# CanBus1apr.net
KiCad netlist of a schematic drawn in EAGLE
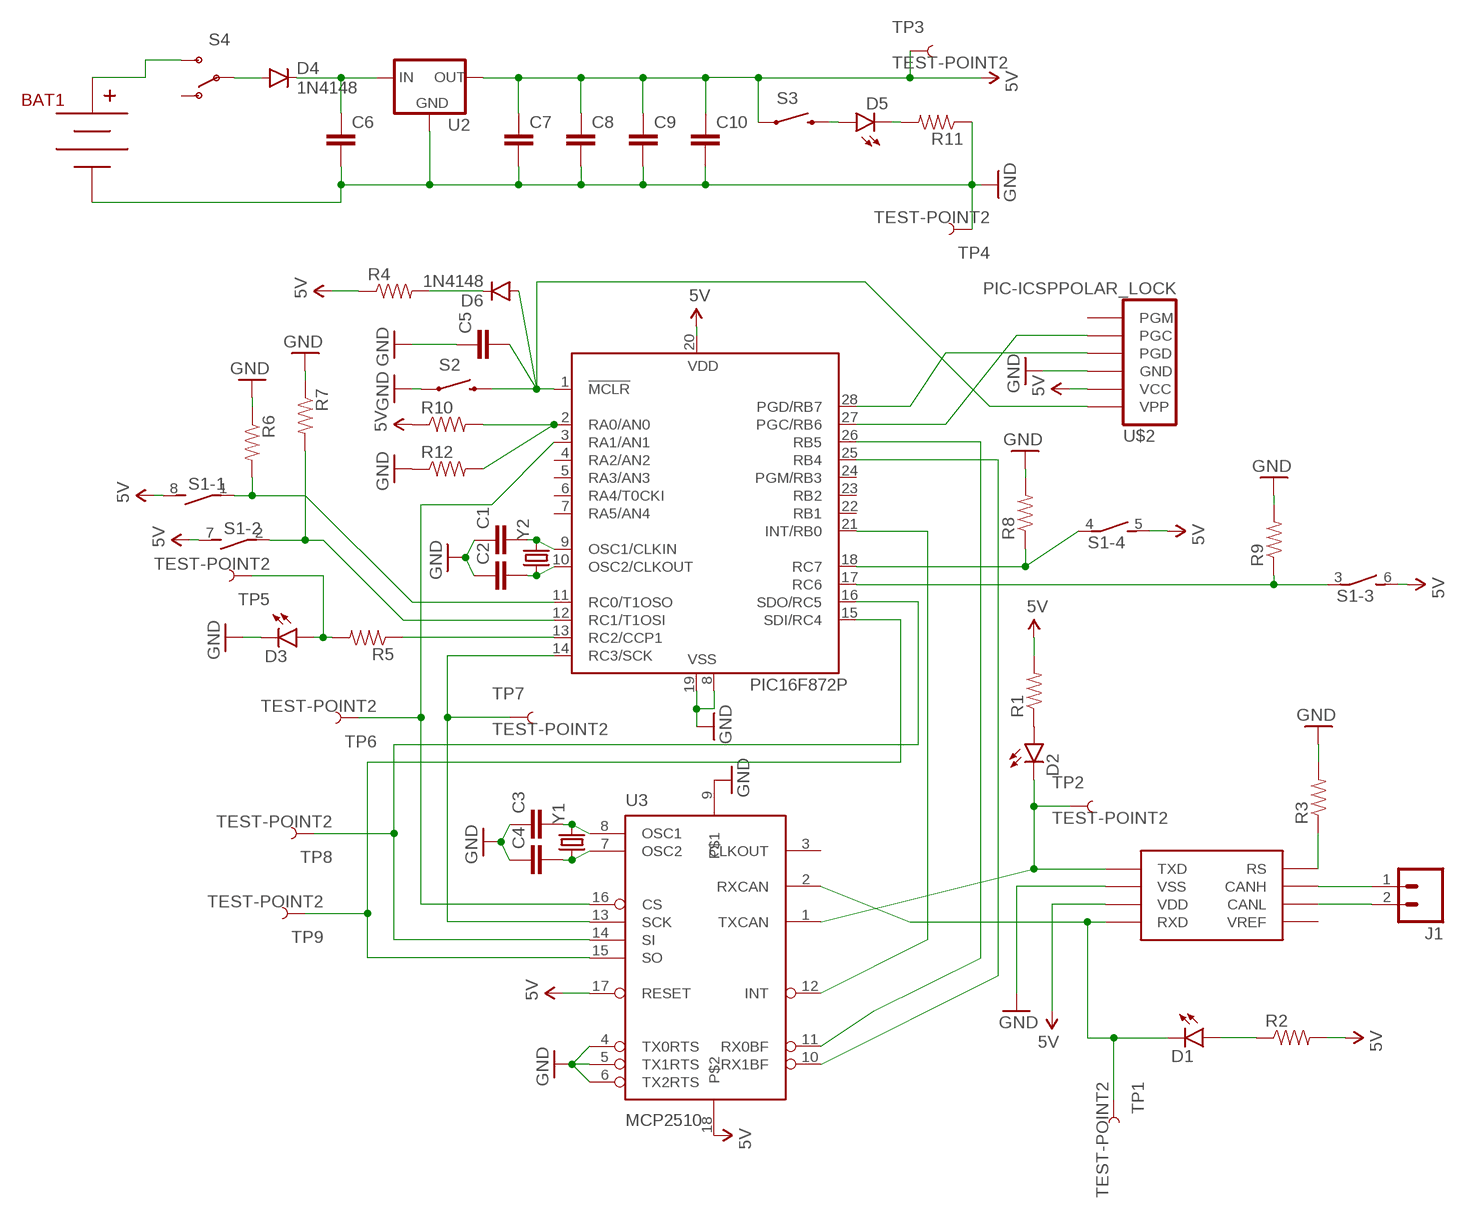
[diagram p0: schematic, sheet 1]

(export (version "E")
  (design (tool "Eeschema 10.0.6"))
  (components
    (comp (ref "BAT1")
      (value "BC9VPC")
      (footprint "eagle-import:BC9VPC")
      (libsource (lib "eagle-import") (part "BC9VPC"))
    )
    (comp (ref "C1")
      (value "CAPPTH")
      (footprint "eagle-import:CAP-PTH-SMALL")
      (libsource (lib "eagle-import") (part "CAPPTH"))
    )
    (comp (ref "C2")
      (value "CAPPTH")
      (footprint "eagle-import:CAP-PTH-SMALL")
      (libsource (lib "eagle-import") (part "CAPPTH"))
    )
    (comp (ref "C3")
      (value "CAPPTH")
      (footprint "eagle-import:CAP-PTH-SMALL")
      (libsource (lib "eagle-import") (part "CAPPTH"))
    )
    (comp (ref "C4")
      (value "CAPPTH")
      (footprint "eagle-import:CAP-PTH-SMALL")
      (libsource (lib "eagle-import") (part "CAPPTH"))
    )
    (comp (ref "C5")
      (value "CAPPTH")
      (footprint "eagle-import:CAP-PTH-SMALL")
      (libsource (lib "eagle-import") (part "CAPPTH"))
    )
    (comp (ref "C6")
      (value "CAPPTH")
      (footprint "eagle-import:CAP-PTH-SMALL")
      (libsource (lib "eagle-import") (part "CAPPTH"))
    )
    (comp (ref "C7")
      (value "CAPPTH")
      (footprint "eagle-import:CAP-PTH-SMALL")
      (libsource (lib "eagle-import") (part "CAPPTH"))
    )
    (comp (ref "C8")
      (value "CAPPTH")
      (footprint "eagle-import:CAP-PTH-SMALL")
      (libsource (lib "eagle-import") (part "CAPPTH"))
    )
    (comp (ref "C9")
      (value "CAPPTH")
      (footprint "eagle-import:CAP-PTH-SMALL")
      (libsource (lib "eagle-import") (part "CAPPTH"))
    )
    (comp (ref "C10")
      (value "CAPPTH")
      (footprint "eagle-import:CAP-PTH-SMALL")
      (libsource (lib "eagle-import") (part "CAPPTH"))
    )
    (comp (ref "D1")
      (value "LED5MM")
      (footprint "eagle-import:LED5MM")
      (libsource (lib "eagle-import") (part "LED5MM"))
    )
    (comp (ref "D2")
      (value "LED5MM")
      (footprint "eagle-import:LED5MM")
      (libsource (lib "eagle-import") (part "LED5MM"))
    )
    (comp (ref "D3")
      (value "LED5MM")
      (footprint "eagle-import:LED5MM")
      (libsource (lib "eagle-import") (part "LED5MM"))
    )
    (comp (ref "D4")
      (value "1N4148")
      (footprint "eagle-import:DIODE-1N4148-KIT")
      (libsource (lib "eagle-import") (part "DIODEKIT"))
    )
    (comp (ref "D5")
      (value "LED5MM")
      (footprint "eagle-import:LED5MM")
      (libsource (lib "eagle-import") (part "LED5MM"))
    )
    (comp (ref "D6")
      (value "1N4148")
      (footprint "eagle-import:DIODE-1N4148-KIT")
      (libsource (lib "eagle-import") (part "DIODEKIT"))
    )
    (comp (ref "IC1")
      (value "PIC16F872P")
      (footprint "eagle-import:DIL28-3")
      (fields (field (name "MF") "MICROCHIP") (field (name "MPN") "PIC16F872-I/SP"))
      (libsource (lib "eagle-import") (part "PIC16872PF"))
    )
    (comp (ref "J1")
      (value "M02PTH")
      (footprint "eagle-import:1X02")
      (libsource (lib "eagle-import") (part "M02PTH"))
    )
    (comp (ref "R1")
      (value "RESISTOREZ")
      (footprint "eagle-import:AXIAL-0.3EZ")
      (libsource (lib "eagle-import") (part "RESISTOREZ"))
    )
    (comp (ref "R2")
      (value "RESISTOREZ")
      (footprint "eagle-import:AXIAL-0.3EZ")
      (libsource (lib "eagle-import") (part "RESISTOREZ"))
    )
    (comp (ref "R3")
      (value "RESISTOREZ")
      (footprint "eagle-import:AXIAL-0.3EZ")
      (libsource (lib "eagle-import") (part "RESISTOREZ"))
    )
    (comp (ref "R4")
      (value "RESISTOREZ")
      (footprint "eagle-import:AXIAL-0.3EZ")
      (libsource (lib "eagle-import") (part "RESISTOREZ"))
    )
    (comp (ref "R5")
      (value "RESISTOREZ")
      (footprint "eagle-import:AXIAL-0.3EZ")
      (libsource (lib "eagle-import") (part "RESISTOREZ"))
    )
    (comp (ref "R6")
      (value "RESISTOREZ")
      (footprint "eagle-import:AXIAL-0.3EZ")
      (libsource (lib "eagle-import") (part "RESISTOREZ"))
    )
    (comp (ref "R7")
      (value "RESISTOREZ")
      (footprint "eagle-import:AXIAL-0.3EZ")
      (libsource (lib "eagle-import") (part "RESISTOREZ"))
    )
    (comp (ref "R8")
      (value "RESISTOREZ")
      (footprint "eagle-import:AXIAL-0.3EZ")
      (libsource (lib "eagle-import") (part "RESISTOREZ"))
    )
    (comp (ref "R9")
      (value "RESISTOREZ")
      (footprint "eagle-import:AXIAL-0.3EZ")
      (libsource (lib "eagle-import") (part "RESISTOREZ"))
    )
    (comp (ref "R10")
      (value "RESISTOREZ")
      (footprint "eagle-import:AXIAL-0.3EZ")
      (libsource (lib "eagle-import") (part "RESISTOREZ"))
    )
    (comp (ref "R11")
      (value "RESISTOREZ")
      (footprint "eagle-import:AXIAL-0.3EZ")
      (libsource (lib "eagle-import") (part "RESISTOREZ"))
    )
    (comp (ref "R12")
      (value "RESISTORAXIAL-0.3")
      (footprint "eagle-import:AXIAL-0.3")
      (libsource (lib "eagle-import") (part "SparkFun-Resistors_RESISTORAXIAL-0.3"))
    )
    (comp (ref "S1")
      (value "DIP04S")
      (footprint "eagle-import:DIP04S")
      (libsource (lib "eagle-import") (part "DIP04S"))
    )
    (comp (ref "S2")
      (value "SWITCH-MOMENTARY-2PTH")
      (footprint "eagle-import:TACTILE-PTH")
      (libsource (lib "eagle-import") (part "SWITCH-MOMENTARY-2PTH"))
    )
    (comp (ref "S3")
      (value "SWITCH-MOMENTARY-2PTH")
      (footprint "eagle-import:TACTILE-PTH")
      (libsource (lib "eagle-import") (part "SWITCH-MOMENTARY-2PTH"))
    )
    (comp (ref "S4")
      (value "SWITCH-SPDTKIT")
      (footprint "eagle-import:SWITCH-SPDT_KIT")
      (libsource (lib "eagle-import") (part "SWITCH-SPDTKIT"))
    )
    (comp (ref "TP1")
      (value "TEST-POINT2")
      (footprint "eagle-import:PAD.02X.02")
      (libsource (lib "eagle-import") (part "TEST-POINT2"))
    )
    (comp (ref "TP2")
      (value "TEST-POINT2")
      (footprint "eagle-import:PAD.02X.02")
      (libsource (lib "eagle-import") (part "TEST-POINT2"))
    )
    (comp (ref "TP3")
      (value "TEST-POINT2")
      (footprint "eagle-import:PAD.02X.02")
      (libsource (lib "eagle-import") (part "TEST-POINT2"))
    )
    (comp (ref "TP4")
      (value "TEST-POINT2")
      (footprint "eagle-import:PAD.02X.02")
      (libsource (lib "eagle-import") (part "TEST-POINT2"))
    )
    (comp (ref "TP5")
      (value "TEST-POINT2")
      (footprint "eagle-import:PAD.02X.02")
      (libsource (lib "eagle-import") (part "TEST-POINT2"))
    )
    (comp (ref "TP6")
      (value "TEST-POINT2")
      (footprint "eagle-import:PAD.02X.02")
      (libsource (lib "eagle-import") (part "TEST-POINT2"))
    )
    (comp (ref "TP7")
      (value "TEST-POINT2")
      (footprint "eagle-import:PAD.02X.02")
      (libsource (lib "eagle-import") (part "TEST-POINT2"))
    )
    (comp (ref "TP8")
      (value "TEST-POINT2")
      (footprint "eagle-import:PAD.02X.02")
      (libsource (lib "eagle-import") (part "TEST-POINT2"))
    )
    (comp (ref "TP9")
      (value "TEST-POINT2")
      (footprint "eagle-import:PAD.02X.02")
      (libsource (lib "eagle-import") (part "TEST-POINT2"))
    )
    (comp (ref "U$1")
      (value "MCP2551")
      (footprint "eagle-import:MCP2551")
      (libsource (lib "eagle-import") (part "MCP2551"))
    )
    (comp (ref "U$2")
      (value "PIC-ICSPPOLAR_LOCK")
      (footprint "eagle-import:MOLEX-1X6_LOCK")
      (libsource (lib "eagle-import") (part "PIC-ICSPPOLAR_LOCK"))
    )
    (comp (ref "U2")
      (value "V_REG_78XXSIDE")
      (footprint "eagle-import:78XXL")
      (libsource (lib "eagle-import") (part "V_REG_78XXSIDE"))
    )
    (comp (ref "U3")
      (value "MCP2510")
      (footprint "eagle-import:DIL18")
      (libsource (lib "eagle-import") (part "MCP2510"))
    )
    (comp (ref "Y1")
      (value "CRYSTALHC49UV")
      (footprint "eagle-import:HC49U-V")
      (libsource (lib "eagle-import") (part "CRYSTALHC49UV"))
    )
    (comp (ref "Y2")
      (value "CRYSTALHC49UV")
      (footprint "eagle-import:HC49U-V")
      (libsource (lib "eagle-import") (part "CRYSTALHC49UV"))
    )
  )
  (nets
    (net (code "1") (name "5V") (class "Default")
      (node (ref "C10") (pin "1") (pinfunction "1_1") (pintype "passive"))
      (node (ref "C7") (pin "1") (pinfunction "1_1") (pintype "passive"))
      (node (ref "C8") (pin "1") (pinfunction "1_1") (pintype "passive"))
      (node (ref "C9") (pin "1") (pinfunction "1_1") (pintype "passive"))
      (node (ref "IC1") (pin "20") (pinfunction "VDD_20") (pintype "power_in"))
      (node (ref "R1") (pin "P$2") (pinfunction "2_P$2") (pintype "passive"))
      (node (ref "R10") (pin "P$1") (pinfunction "1_P$1") (pintype "passive"))
      (node (ref "R2") (pin "P$2") (pinfunction "2_P$2") (pintype "passive"))
      (node (ref "R4") (pin "P$1") (pinfunction "1_P$1") (pintype "passive"))
      (node (ref "S1") (pin "5") (pinfunction "2_5") (pintype "passive"))
      (node (ref "S1") (pin "6") (pinfunction "2_6") (pintype "passive"))
      (node (ref "S1") (pin "7") (pinfunction "2_7") (pintype "passive"))
      (node (ref "S1") (pin "8") (pinfunction "2_8") (pintype "passive"))
      (node (ref "S3") (pin "1") (pinfunction "1_1") (pintype "passive"))
      (node (ref "TP3") (pin "P$1") (pinfunction "1_P$1") (pintype "bidirectional"))
      (node (ref "U$1") (pin "VDD") (pinfunction "VDD_VDD") (pintype "bidirectional"))
      (node (ref "U$2") (pin "5") (pinfunction "VCC_5") (pintype "bidirectional"))
      (node (ref "U2") (pin "OUT") (pinfunction "OUT_OUT") (pintype "passive"))
      (node (ref "U3") (pin "17") (pinfunction "RESET_17") (pintype "input"))
      (node (ref "U3") (pin "18") (pinfunction "P$2_18") (pintype "bidirectional"))
    )
    (net (code "2") (name "GND") (class "Default")
      (node (ref "BAT1") (pin "V-") (pinfunction "V-_V-") (pintype "bidirectional"))
      (node (ref "C1") (pin "1") (pinfunction "1_1") (pintype "passive"))
      (node (ref "C10") (pin "2") (pinfunction "2_2") (pintype "passive"))
      (node (ref "C2") (pin "1") (pinfunction "1_1") (pintype "passive"))
      (node (ref "C3") (pin "1") (pinfunction "1_1") (pintype "passive"))
      (node (ref "C4") (pin "1") (pinfunction "1_1") (pintype "passive"))
      (node (ref "C5") (pin "1") (pinfunction "1_1") (pintype "passive"))
      (node (ref "C6") (pin "2") (pinfunction "2_2") (pintype "passive"))
      (node (ref "C7") (pin "2") (pinfunction "2_2") (pintype "passive"))
      (node (ref "C8") (pin "2") (pinfunction "2_2") (pintype "passive"))
      (node (ref "C9") (pin "2") (pinfunction "2_2") (pintype "passive"))
      (node (ref "D3") (pin "K") (pinfunction "C_K") (pintype "passive"))
      (node (ref "IC1") (pin "19") (pinfunction "VSS_19") (pintype "power_in"))
      (node (ref "IC1") (pin "8") (pinfunction "VSS_8") (pintype "power_in"))
      (node (ref "R11") (pin "P$1") (pinfunction "1_P$1") (pintype "passive"))
      (node (ref "R12") (pin "P$1") (pinfunction "1_P$1") (pintype "passive"))
      (node (ref "R3") (pin "P$2") (pinfunction "2_P$2") (pintype "passive"))
      (node (ref "R6") (pin "P$1") (pinfunction "1_P$1") (pintype "passive"))
      (node (ref "R7") (pin "P$1") (pinfunction "1_P$1") (pintype "passive"))
      (node (ref "R8") (pin "P$2") (pinfunction "2_P$2") (pintype "passive"))
      (node (ref "R9") (pin "P$2") (pinfunction "2_P$2") (pintype "passive"))
      (node (ref "S2") (pin "1") (pinfunction "1_1") (pintype "passive"))
      (node (ref "TP4") (pin "P$1") (pinfunction "1_P$1") (pintype "bidirectional"))
      (node (ref "U$1") (pin "VSS") (pinfunction "VSS_VSS") (pintype "bidirectional"))
      (node (ref "U$2") (pin "4") (pinfunction "GND_4") (pintype "bidirectional"))
      (node (ref "U2") (pin "GND") (pinfunction "GND_GND") (pintype "input"))
      (node (ref "U3") (pin "4") (pinfunction "TX0RTS_4") (pintype "input"))
      (node (ref "U3") (pin "5") (pinfunction "TX1RTS_5") (pintype "input"))
      (node (ref "U3") (pin "6") (pinfunction "TX2RTS_6") (pintype "input"))
      (node (ref "U3") (pin "9") (pinfunction "P$1_9") (pintype "bidirectional"))
    )
    (net (code "3") (name "Net-(C6-Pad1)") (class "Default")
      (node (ref "C6") (pin "1") (pinfunction "1_1") (pintype "passive"))
      (node (ref "D4") (pin "C") (pinfunction "C_C") (pintype "passive"))
      (node (ref "U2") (pin "IN") (pinfunction "IN_IN") (pintype "input"))
    )
    (net (code "4") (name "Net-(D1-C)") (class "Default")
      (node (ref "D1") (pin "K") (pinfunction "C_K") (pintype "passive"))
      (node (ref "TP1") (pin "P$1") (pinfunction "1_P$1") (pintype "bidirectional"))
      (node (ref "U$1") (pin "RXD") (pinfunction "RXD_RXD") (pintype "bidirectional"))
      (node (ref "U3") (pin "2") (pinfunction "RXCAN_2") (pintype "input"))
    )
    (net (code "5") (name "Net-(D2-C)") (class "Default")
      (node (ref "D2") (pin "K") (pinfunction "C_K") (pintype "passive"))
      (node (ref "TP2") (pin "P$1") (pinfunction "1_P$1") (pintype "bidirectional"))
      (node (ref "U$1") (pin "TXD") (pinfunction "TXD_TXD") (pintype "bidirectional"))
      (node (ref "U3") (pin "1") (pinfunction "TXCAN_1") (pintype "output"))
    )
    (net (code "6") (name "Net-(D5-C)") (class "Default")
      (node (ref "D5") (pin "K") (pinfunction "C_K") (pintype "passive"))
      (node (ref "R11") (pin "P$2") (pinfunction "2_P$2") (pintype "passive"))
    )
    (net (code "7") (name "Net-(IC1-INT{slash}RB0)") (class "Default")
      (node (ref "IC1") (pin "21") (pinfunction "INT/RB0_21") (pintype "bidirectional"))
      (node (ref "U3") (pin "12") (pinfunction "INT_12") (pintype "output"))
    )
    (net (code "8") (name "Net-(IC1-OSC1{slash}CLKIN)") (class "Default")
      (node (ref "C1") (pin "2") (pinfunction "2_2") (pintype "passive"))
      (node (ref "IC1") (pin "9") (pinfunction "OSC1/CLKIN_9") (pintype "input"))
      (node (ref "Y2") (pin "2") (pinfunction "2_2") (pintype "passive"))
    )
    (net (code "9") (name "Net-(IC1-OSC2{slash}CLKOUT)") (class "Default")
      (node (ref "C2") (pin "2") (pinfunction "2_2") (pintype "passive"))
      (node (ref "IC1") (pin "10") (pinfunction "OSC2/CLKOUT_10") (pintype "output"))
      (node (ref "Y2") (pin "1") (pinfunction "1_1") (pintype "passive"))
    )
    (net (code "10") (name "Net-(IC1-PGC{slash}RB6)") (class "Default")
      (node (ref "IC1") (pin "27") (pinfunction "PGC/RB6_27") (pintype "bidirectional"))
      (node (ref "U$2") (pin "2") (pinfunction "PGC_2") (pintype "bidirectional"))
    )
    (net (code "11") (name "Net-(IC1-PGD{slash}RB7)") (class "Default")
      (node (ref "IC1") (pin "28") (pinfunction "PGD/RB7_28") (pintype "bidirectional"))
      (node (ref "U$2") (pin "3") (pinfunction "PGD_3") (pintype "bidirectional"))
    )
    (net (code "12") (name "Net-(IC1-RA0{slash}AN0)") (class "Default")
      (node (ref "IC1") (pin "2") (pinfunction "RA0/AN0_2") (pintype "bidirectional"))
      (node (ref "R10") (pin "P$2") (pinfunction "2_P$2") (pintype "passive"))
      (node (ref "R12") (pin "P$2") (pinfunction "2_P$2") (pintype "passive"))
    )
    (net (code "13") (name "Net-(IC1-RA1{slash}AN1)") (class "Default")
      (node (ref "IC1") (pin "3") (pinfunction "RA1/AN1_3") (pintype "bidirectional"))
      (node (ref "TP6") (pin "P$1") (pinfunction "1_P$1") (pintype "bidirectional"))
      (node (ref "U3") (pin "16") (pinfunction "CS_16") (pintype "input"))
    )
    (net (code "14") (name "Net-(IC1-RB4)") (class "Default")
      (node (ref "IC1") (pin "25") (pinfunction "RB4_25") (pintype "bidirectional"))
      (node (ref "U3") (pin "10") (pinfunction "RX1BF_10") (pintype "output"))
    )
    (net (code "15") (name "Net-(IC1-RB5)") (class "Default")
      (node (ref "IC1") (pin "26") (pinfunction "RB5_26") (pintype "bidirectional"))
      (node (ref "U3") (pin "11") (pinfunction "RX0BF_11") (pintype "output"))
    )
    (net (code "16") (name "Net-(IC1-RC0{slash}T1OSO)") (class "Default")
      (node (ref "IC1") (pin "11") (pinfunction "RC0/T1OSO_11") (pintype "bidirectional"))
      (node (ref "R6") (pin "P$2") (pinfunction "2_P$2") (pintype "passive"))
      (node (ref "S1") (pin "1") (pinfunction "1_1") (pintype "passive"))
    )
    (net (code "17") (name "Net-(IC1-RC1{slash}T1OSI)") (class "Default")
      (node (ref "IC1") (pin "12") (pinfunction "RC1/T1OSI_12") (pintype "bidirectional"))
      (node (ref "R7") (pin "P$2") (pinfunction "2_P$2") (pintype "passive"))
      (node (ref "S1") (pin "2") (pinfunction "1_2") (pintype "passive"))
    )
    (net (code "18") (name "Net-(IC1-RC2{slash}CCP1)") (class "Default")
      (node (ref "IC1") (pin "13") (pinfunction "RC2/CCP1_13") (pintype "bidirectional"))
      (node (ref "R5") (pin "P$1") (pinfunction "1_P$1") (pintype "passive"))
    )
    (net (code "19") (name "Net-(IC1-RC3{slash}SCK)") (class "Default")
      (node (ref "IC1") (pin "14") (pinfunction "RC3/SCK_14") (pintype "bidirectional"))
      (node (ref "TP7") (pin "P$1") (pinfunction "1_P$1") (pintype "bidirectional"))
      (node (ref "U3") (pin "13") (pinfunction "SCK_13") (pintype "input"))
    )
    (net (code "20") (name "Net-(IC1-RC6)") (class "Default")
      (node (ref "IC1") (pin "17") (pinfunction "RC6_17") (pintype "bidirectional"))
      (node (ref "R9") (pin "P$1") (pinfunction "1_P$1") (pintype "passive"))
      (node (ref "S1") (pin "3") (pinfunction "1_3") (pintype "passive"))
    )
    (net (code "21") (name "Net-(IC1-RC7)") (class "Default")
      (node (ref "IC1") (pin "18") (pinfunction "RC7_18") (pintype "bidirectional"))
      (node (ref "R8") (pin "P$1") (pinfunction "1_P$1") (pintype "passive"))
      (node (ref "S1") (pin "4") (pinfunction "1_4") (pintype "passive"))
    )
    (net (code "22") (name "Net-(IC1-SDI{slash}RC4)") (class "Default")
      (node (ref "IC1") (pin "15") (pinfunction "SDI/RC4_15") (pintype "bidirectional"))
      (node (ref "TP9") (pin "P$1") (pinfunction "1_P$1") (pintype "bidirectional"))
      (node (ref "U3") (pin "15") (pinfunction "SO_15") (pintype "output"))
    )
    (net (code "23") (name "Net-(IC1-SDO{slash}RC5)") (class "Default")
      (node (ref "IC1") (pin "16") (pinfunction "SDO/RC5_16") (pintype "bidirectional"))
      (node (ref "TP8") (pin "P$1") (pinfunction "1_P$1") (pintype "bidirectional"))
      (node (ref "U3") (pin "14") (pinfunction "SI_14") (pintype "input"))
    )
    (net (code "24") (name "Net-(IC1-~{MCLR})") (class "Default")
      (node (ref "C5") (pin "2") (pinfunction "2_2") (pintype "passive"))
      (node (ref "D6") (pin "A") (pinfunction "A_A") (pintype "passive"))
      (node (ref "IC1") (pin "1") (pinfunction "~{MCLR}_1") (pintype "input"))
      (node (ref "S2") (pin "3") (pinfunction "2_3") (pintype "passive"))
      (node (ref "U$2") (pin "6") (pinfunction "VPP_6") (pintype "bidirectional"))
    )
    (net (code "25") (name "Net-(J1-Pad1)") (class "Default")
      (node (ref "J1") (pin "1") (pinfunction "1_1") (pintype "passive"))
      (node (ref "U$1") (pin "CANH") (pinfunction "CANH_CANH") (pintype "bidirectional"))
    )
    (net (code "26") (name "Net-(J1-Pad2)") (class "Default")
      (node (ref "J1") (pin "2") (pinfunction "2_2") (pintype "passive"))
      (node (ref "U$1") (pin "CANL") (pinfunction "CANL_CANL") (pintype "bidirectional"))
    )
    (net (code "27") (name "Net-(R1-1)") (class "Default")
      (node (ref "D2") (pin "A") (pinfunction "A_A") (pintype "passive"))
      (node (ref "R1") (pin "P$1") (pinfunction "1_P$1") (pintype "passive"))
    )
    (net (code "28") (name "Net-(R2-1)") (class "Default")
      (node (ref "D1") (pin "A") (pinfunction "A_A") (pintype "passive"))
      (node (ref "R2") (pin "P$1") (pinfunction "1_P$1") (pintype "passive"))
    )
    (net (code "29") (name "Net-(R3-1)") (class "Default")
      (node (ref "R3") (pin "P$1") (pinfunction "1_P$1") (pintype "passive"))
      (node (ref "U$1") (pin "RS") (pinfunction "RS_RS") (pintype "bidirectional"))
    )
    (net (code "30") (name "Net-(R4-2)") (class "Default")
      (node (ref "D6") (pin "C") (pinfunction "C_C") (pintype "passive"))
      (node (ref "R4") (pin "P$2") (pinfunction "2_P$2") (pintype "passive"))
    )
    (net (code "31") (name "Net-(R5-2)") (class "Default")
      (node (ref "D3") (pin "A") (pinfunction "A_A") (pintype "passive"))
      (node (ref "R5") (pin "P$2") (pinfunction "2_P$2") (pintype "passive"))
      (node (ref "TP5") (pin "P$1") (pinfunction "1_P$1") (pintype "bidirectional"))
    )
    (net (code "32") (name "Net-(S3-2)") (class "Default")
      (node (ref "D5") (pin "A") (pinfunction "A_A") (pintype "passive"))
      (node (ref "S3") (pin "3") (pinfunction "2_3") (pintype "passive"))
    )
    (net (code "33") (name "Net-(S4-P)") (class "Default")
      (node (ref "D4") (pin "A") (pinfunction "A_A") (pintype "passive"))
      (node (ref "S4") (pin "2") (pinfunction "P_2") (pintype "passive"))
    )
    (net (code "34") (name "Net-(S4-S)") (class "Default")
      (node (ref "BAT1") (pin "V+") (pinfunction "V+_V+") (pintype "bidirectional"))
      (node (ref "S4") (pin "3") (pinfunction "S_3") (pintype "passive"))
    )
    (net (code "35") (name "Net-(U3-OSC1)") (class "Default")
      (node (ref "C3") (pin "2") (pinfunction "2_2") (pintype "passive"))
      (node (ref "U3") (pin "8") (pinfunction "OSC1_8") (pintype "input"))
      (node (ref "Y1") (pin "2") (pinfunction "2_2") (pintype "passive"))
    )
    (net (code "36") (name "Net-(U3-OSC2)") (class "Default")
      (node (ref "C4") (pin "2") (pinfunction "2_2") (pintype "passive"))
      (node (ref "U3") (pin "7") (pinfunction "OSC2_7") (pintype "output"))
      (node (ref "Y1") (pin "1") (pinfunction "1_1") (pintype "passive"))
    )
    (net (code "37") (name "unconnected-(IC1-PGM{slash}RB3-Pad24)") (class "Default")
      (node (ref "IC1") (pin "24") (pinfunction "PGM/RB3_24") (pintype "bidirectional"))
    )
    (net (code "38") (name "unconnected-(IC1-RA2{slash}AN2-Pad4)") (class "Default")
      (node (ref "IC1") (pin "4") (pinfunction "RA2/AN2_4") (pintype "bidirectional"))
    )
    (net (code "39") (name "unconnected-(IC1-RA3{slash}AN3-Pad5)") (class "Default")
      (node (ref "IC1") (pin "5") (pinfunction "RA3/AN3_5") (pintype "bidirectional"))
    )
    (net (code "40") (name "unconnected-(IC1-RA4{slash}T0CKI-Pad6)") (class "Default")
      (node (ref "IC1") (pin "6") (pinfunction "RA4/T0CKI_6") (pintype "bidirectional"))
    )
    (net (code "41") (name "unconnected-(IC1-RA5{slash}AN4-Pad7)") (class "Default")
      (node (ref "IC1") (pin "7") (pinfunction "RA5/AN4_7") (pintype "bidirectional"))
    )
    (net (code "42") (name "unconnected-(IC1-RB1-Pad22)") (class "Default")
      (node (ref "IC1") (pin "22") (pinfunction "RB1_22") (pintype "bidirectional"))
    )
    (net (code "43") (name "unconnected-(IC1-RB2-Pad23)") (class "Default")
      (node (ref "IC1") (pin "23") (pinfunction "RB2_23") (pintype "bidirectional"))
    )
    (net (code "44") (name "unconnected-(S4-O-Pad1)") (class "Default")
      (node (ref "S4") (pin "1") (pinfunction "O_1") (pintype "passive"))
    )
    (net (code "45") (name "unconnected-(U$1-PadVREF)") (class "Default")
      (node (ref "U$1") (pin "VREF") (pinfunction "VREF_VREF") (pintype "bidirectional"))
    )
    (net (code "46") (name "unconnected-(U$2-PGM-Pad1)") (class "Default")
      (node (ref "U$2") (pin "1") (pinfunction "PGM_1") (pintype "bidirectional"))
    )
    (net (code "47") (name "unconnected-(U3-CLKOUT-Pad3)") (class "Default")
      (node (ref "U3") (pin "3") (pinfunction "CLKOUT_3") (pintype "output"))
    )
  )
)
